# untitled.net
KiCad netlist of a schematic drawn in EAGLE
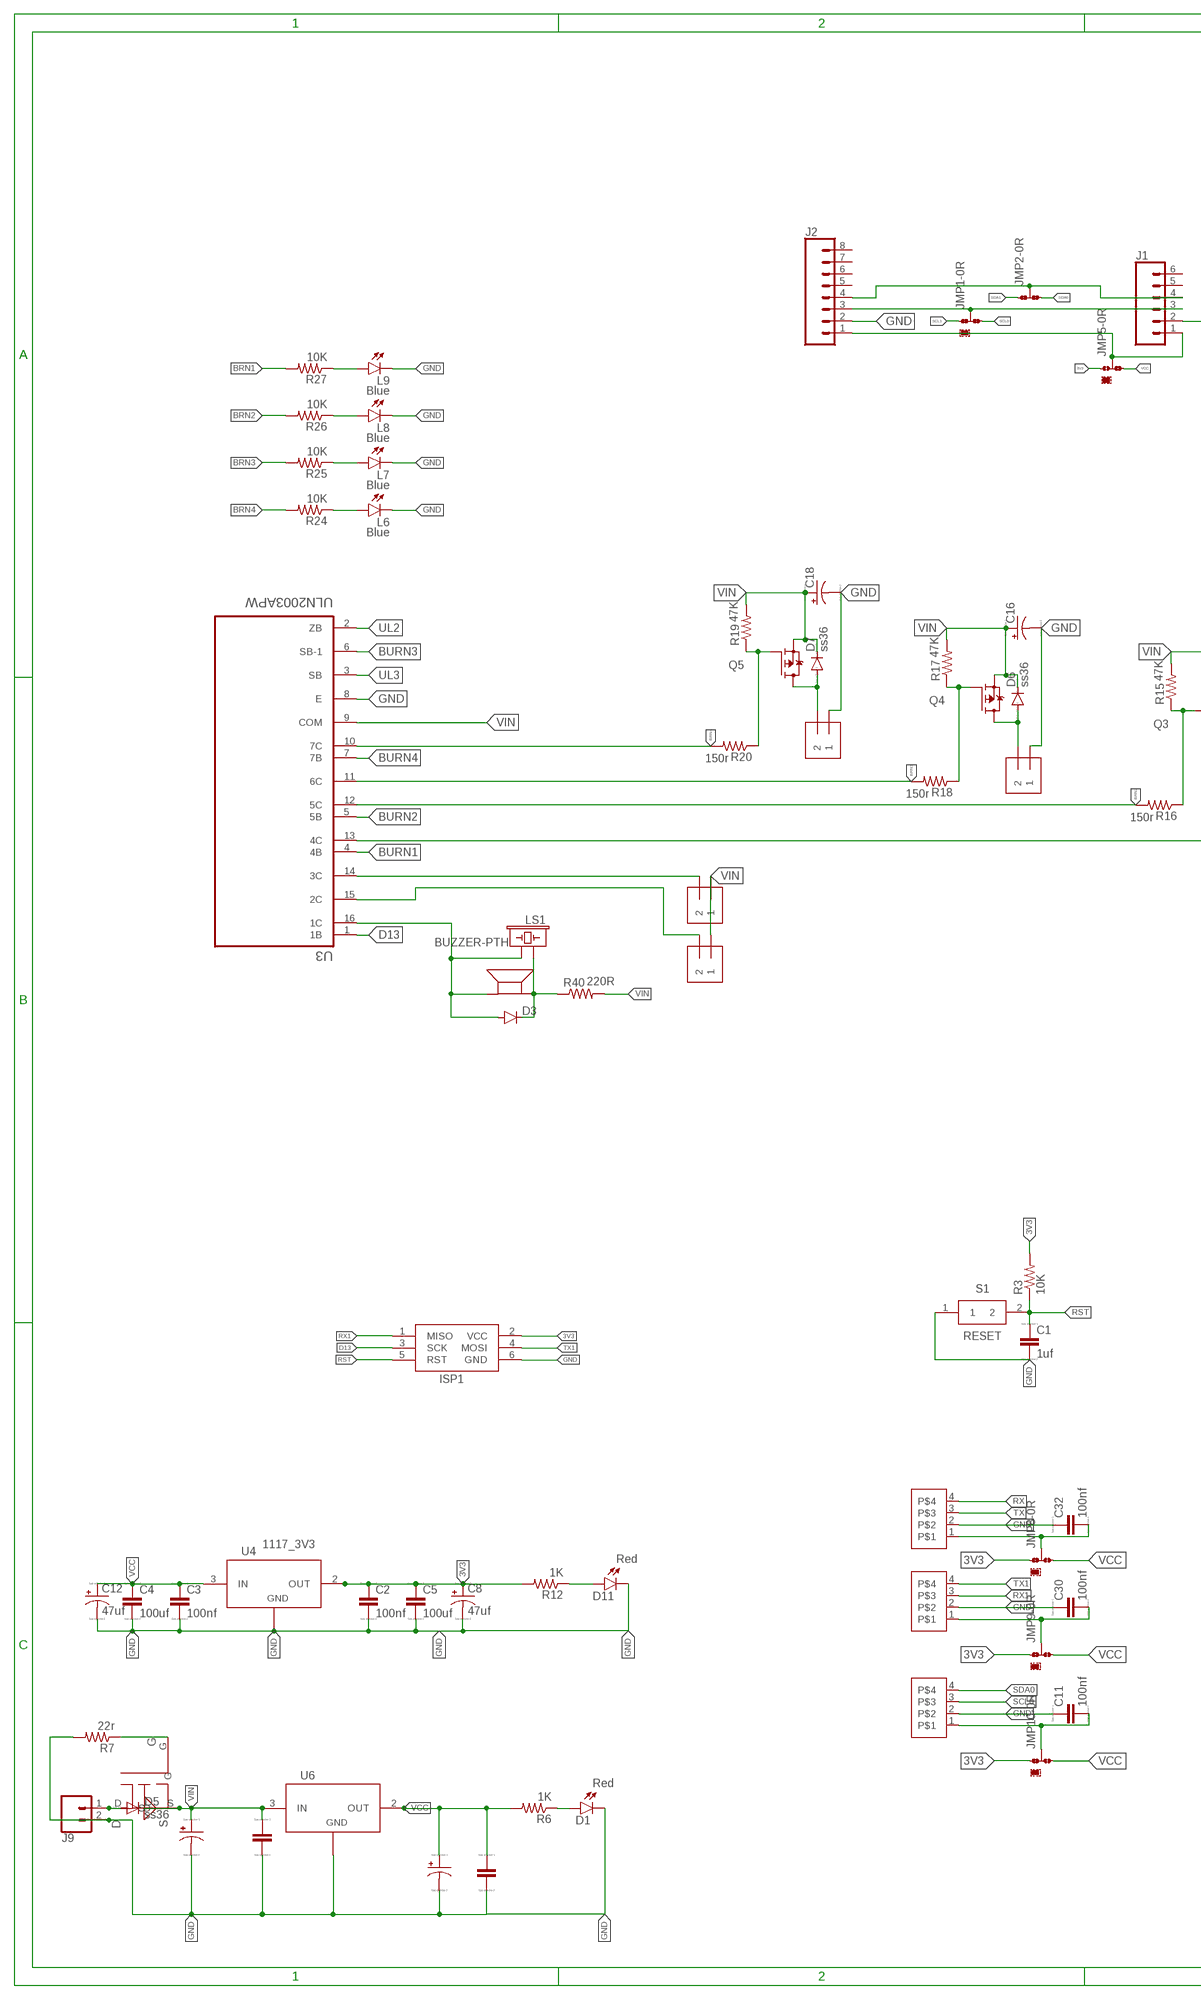
[diagram p0: schematic, sheet 1, part 1 of 2]
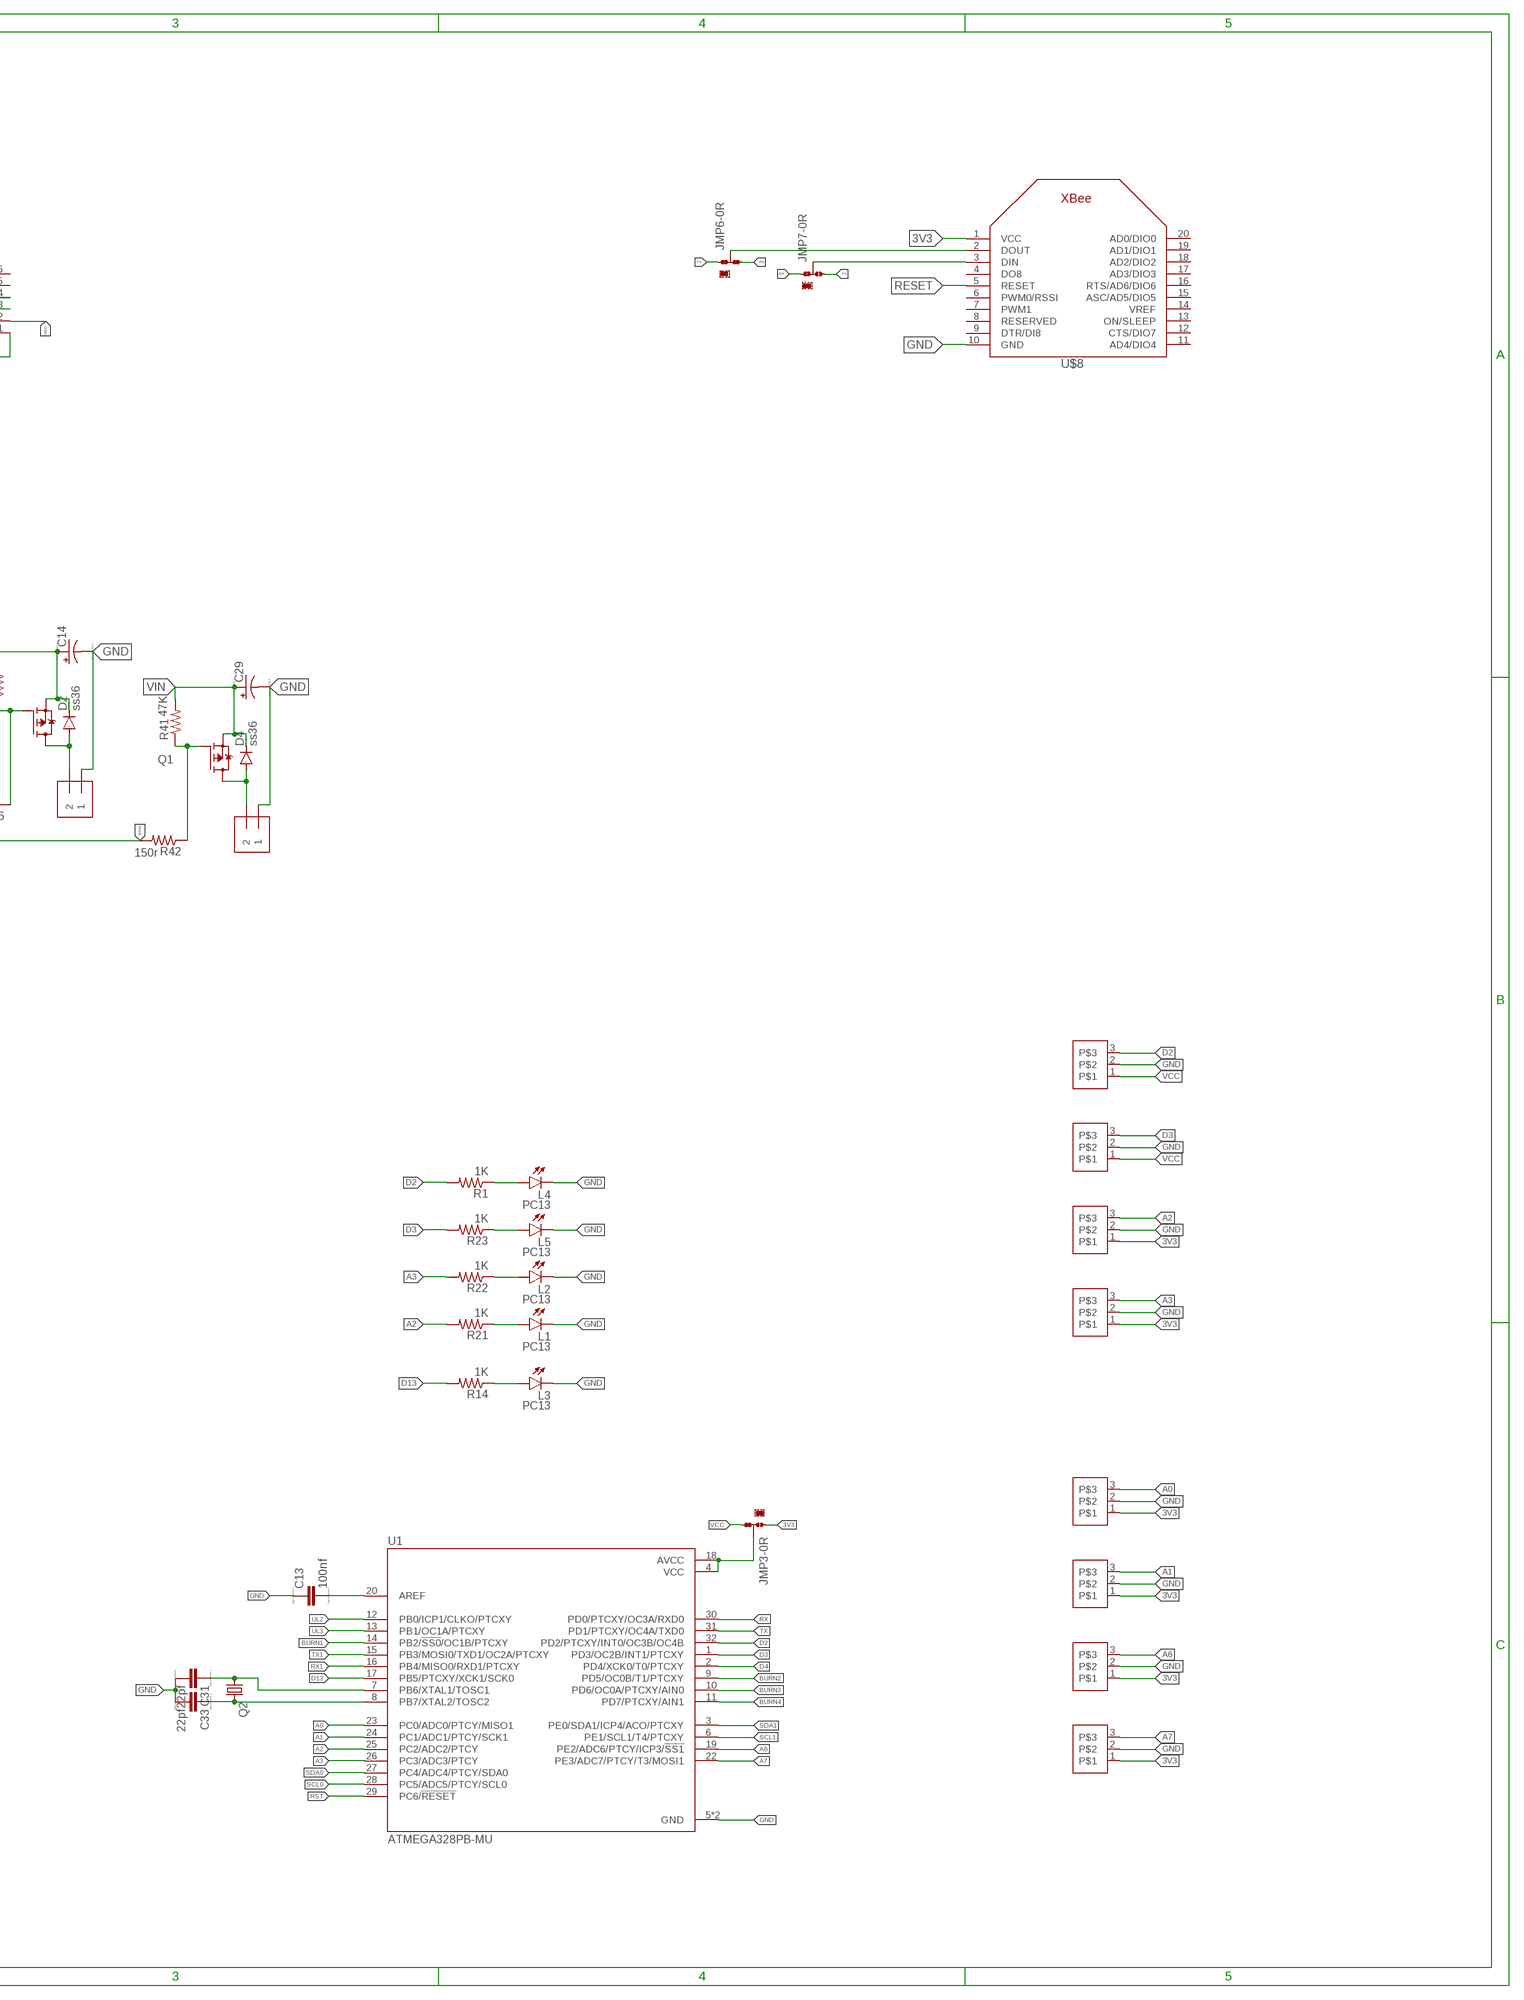
[diagram p1: schematic, sheet 1, part 2 of 2]

(export (version "E")
  (design (tool "Eeschema 10.0.6"))
  (components
    (comp (ref "C1")
      (value "1uf")
      (footprint "eagle-import:C0603")
      (libsource (lib "eagle-import") (part "CAPACITOR_CER4"))
    )
    (comp (ref "C2")
      (value "100nf")
      (footprint "eagle-import:C0603")
      (libsource (lib "eagle-import") (part "CAPACITOR_CER4"))
    )
    (comp (ref "C3")
      (value "100nf")
      (footprint "eagle-import:C0603")
      (libsource (lib "eagle-import") (part "CAPACITOR_CER4"))
    )
    (comp (ref "C4")
      (value "100uf")
      (footprint "eagle-import:C1210")
      (libsource (lib "eagle-import") (part "CAPACITOR_CER9"))
    )
    (comp (ref "C5")
      (value "100uf")
      (footprint "eagle-import:C1210")
      (libsource (lib "eagle-import") (part "CAPACITOR_CER9"))
    )
    (comp (ref "C6")
      (value "100nf")
      (footprint "eagle-import:C0603")
      (libsource (lib "eagle-import") (part "CAPACITOR_CER4"))
    )
    (comp (ref "C7")
      (value "100uf")
      (footprint "eagle-import:PANASONIC_D")
      (libsource (lib "eagle-import") (part "CAPACITOR_POLD"))
    )
    (comp (ref "C8")
      (value "47uf")
      (footprint "eagle-import:PANASONIC_C")
      (libsource (lib "eagle-import") (part "CAPACITOR_POLC"))
    )
    (comp (ref "C9")
      (value "100nf")
      (footprint "eagle-import:C0603")
      (libsource (lib "eagle-import") (part "CAPACITOR_CER4"))
    )
    (comp (ref "C10")
      (value "100uf")
      (footprint "eagle-import:PANASONIC_D")
      (libsource (lib "eagle-import") (part "CAPACITOR_POLD"))
    )
    (comp (ref "C11")
      (value "100nf")
      (footprint "eagle-import:C0603")
      (libsource (lib "eagle-import") (part "CAPACITOR_CER4"))
    )
    (comp (ref "C12")
      (value "47uf")
      (footprint "eagle-import:PANASONIC_C")
      (libsource (lib "eagle-import") (part "CAPACITOR_POLC"))
    )
    (comp (ref "C13")
      (value "100nf")
      (footprint "eagle-import:C0603")
      (libsource (lib "eagle-import") (part "CAPACITOR_CER4"))
    )
    (comp (ref "C14")
      (value "CAPACITOR_POLC")
      (footprint "eagle-import:PANASONIC_C")
      (libsource (lib "eagle-import") (part "CAPACITOR_POLC"))
    )
    (comp (ref "C16")
      (value "CAPACITOR_POLC")
      (footprint "eagle-import:PANASONIC_C")
      (libsource (lib "eagle-import") (part "CAPACITOR_POLC"))
    )
    (comp (ref "C18")
      (value "CAPACITOR_POLC")
      (footprint "eagle-import:PANASONIC_C")
      (libsource (lib "eagle-import") (part "CAPACITOR_POLC"))
    )
    (comp (ref "C29")
      (value "CAPACITOR_POLC")
      (footprint "eagle-import:PANASONIC_C")
      (libsource (lib "eagle-import") (part "CAPACITOR_POLC"))
    )
    (comp (ref "C30")
      (value "100nf")
      (footprint "eagle-import:C0603")
      (libsource (lib "eagle-import") (part "CAPACITOR_CER4"))
    )
    (comp (ref "C31")
      (value "22pf")
      (footprint "eagle-import:C0603")
      (libsource (lib "eagle-import") (part "CAPACITOR_CER4"))
    )
    (comp (ref "C32")
      (value "100nf")
      (footprint "eagle-import:C0603")
      (libsource (lib "eagle-import") (part "CAPACITOR_CER4"))
    )
    (comp (ref "C33")
      (value "22pf")
      (footprint "eagle-import:C0603")
      (libsource (lib "eagle-import") (part "CAPACITOR_CER4"))
    )
    (comp (ref "D1")
      (value "Red")
      (footprint "eagle-import:0603_LED_GREEN")
      (libsource (lib "eagle-import") (part "LED0603_R"))
    )
    (comp (ref "D2")
      (value "ss36")
      (footprint "eagle-import:DO-214AC")
      (libsource (lib "eagle-import") (part "DIODEAC2"))
    )
    (comp (ref "D3")
      (value "DIODESOD")
      (footprint "eagle-import:SOD-323")
      (libsource (lib "eagle-import") (part "DIODESOD"))
    )
    (comp (ref "D4")
      (value "ss36")
      (footprint "eagle-import:DO-214AC")
      (libsource (lib "eagle-import") (part "DIODEAC2"))
    )
    (comp (ref "D5")
      (value "ss36")
      (footprint "eagle-import:DO-214AC")
      (libsource (lib "eagle-import") (part "DIODEAC2"))
    )
    (comp (ref "D6")
      (value "ss36")
      (footprint "eagle-import:DO-214AC")
      (libsource (lib "eagle-import") (part "DIODEAC2"))
    )
    (comp (ref "D7")
      (value "ss36")
      (footprint "eagle-import:DO-214AC")
      (libsource (lib "eagle-import") (part "DIODEAC2"))
    )
    (comp (ref "D11")
      (value "Red")
      (footprint "eagle-import:0603_LED_GREEN")
      (libsource (lib "eagle-import") (part "LED0603_R"))
    )
    (comp (ref "ISP1")
      (value "AVRISP-6")
      (footprint "eagle-import:AVRISP")
      (libsource (lib "eagle-import") (part "AVRISP-6"))
    )
    (comp (ref "J1")
      (value "CONN_06NO_SILK_NO_POP")
      (footprint "eagle-import:1X06_NO_SILK")
      (libsource (lib "eagle-import") (part "CONN_06NO_SILK_NO_POP"))
    )
    (comp (ref "J2")
      (value "CONN_08NO_SILK_FEMALE_PTH")
      (footprint "eagle-import:1X08_NO_SILK")
      (libsource (lib "eagle-import") (part "CONN_08NO_SILK_FEMALE_PTH"))
    )
    (comp (ref "J9")
      (value "CONN_025MM")
      (footprint "eagle-import:SCREWTERMINAL-5MM-2")
      (libsource (lib "eagle-import") (part "CONN_025MM"))
    )
    (comp (ref "JMP1")
      (value "0R-JUMPA")
      (footprint "eagle-import:A0R-JMP")
      (libsource (lib "eagle-import") (part "0R-JUMPA"))
    )
    (comp (ref "JMP2")
      (value "0R-JUMPA")
      (footprint "eagle-import:A0R-JMP")
      (libsource (lib "eagle-import") (part "0R-JUMPA"))
    )
    (comp (ref "JMP3")
      (value "0R-JUMPA")
      (footprint "eagle-import:A0R-JMP")
      (libsource (lib "eagle-import") (part "0R-JUMPA"))
    )
    (comp (ref "JMP5")
      (value "0R-JUMPA")
      (footprint "eagle-import:A0R-JMP")
      (libsource (lib "eagle-import") (part "0R-JUMPA"))
    )
    (comp (ref "JMP6")
      (value "0R-JUMPA")
      (footprint "eagle-import:A0R-JMP")
      (libsource (lib "eagle-import") (part "0R-JUMPA"))
    )
    (comp (ref "JMP7")
      (value "0R-JUMPA")
      (footprint "eagle-import:A0R-JMP")
      (libsource (lib "eagle-import") (part "0R-JUMPA"))
    )
    (comp (ref "JMP8")
      (value "0R-JUMPA")
      (footprint "eagle-import:A0R-JMP")
      (libsource (lib "eagle-import") (part "0R-JUMPA"))
    )
    (comp (ref "JMP9")
      (value "0R-JUMPA")
      (footprint "eagle-import:A0R-JMP")
      (libsource (lib "eagle-import") (part "0R-JUMPA"))
    )
    (comp (ref "JMP10")
      (value "0R-JUMPA")
      (footprint "eagle-import:A0R-JMP")
      (libsource (lib "eagle-import") (part "0R-JUMPA"))
    )
    (comp (ref "L1")
      (value "PC13")
      (footprint "eagle-import:0603_LED_GREEN")
      (libsource (lib "eagle-import") (part "LED0603_R"))
    )
    (comp (ref "L2")
      (value "PC13")
      (footprint "eagle-import:0603_LED_GREEN")
      (libsource (lib "eagle-import") (part "LED0603_R"))
    )
    (comp (ref "L3")
      (value "PC13")
      (footprint "eagle-import:0603_LED_GREEN")
      (libsource (lib "eagle-import") (part "LED0603_R"))
    )
    (comp (ref "L4")
      (value "PC13")
      (footprint "eagle-import:0603_LED_GREEN")
      (libsource (lib "eagle-import") (part "LED0603_R"))
    )
    (comp (ref "L5")
      (value "PC13")
      (footprint "eagle-import:0603_LED_GREEN")
      (libsource (lib "eagle-import") (part "LED0603_R"))
    )
    (comp (ref "L6")
      (value "Blue")
      (footprint "eagle-import:0603_LED_GREEN")
      (libsource (lib "eagle-import") (part "LED0603_R"))
    )
    (comp (ref "L7")
      (value "Blue")
      (footprint "eagle-import:0603_LED_GREEN")
      (libsource (lib "eagle-import") (part "LED0603_R"))
    )
    (comp (ref "L8")
      (value "Blue")
      (footprint "eagle-import:0603_LED_GREEN")
      (libsource (lib "eagle-import") (part "LED0603_R"))
    )
    (comp (ref "L9")
      (value "Blue")
      (footprint "eagle-import:0603_LED_GREEN")
      (libsource (lib "eagle-import") (part "LED0603_R"))
    )
    (comp (ref "LS1")
      (value "BUZZER-PTH")
      (footprint "eagle-import:BUZZER-12MM")
      (libsource (lib "eagle-import") (part "BUZZER-PTH"))
    )
    (comp (ref "Q1")
      (value "FDD4141TO252")
      (footprint "eagle-import:TO252")
      (libsource (lib "eagle-import") (part "FDD4141TO252"))
    )
    (comp (ref "Q2")
      (value "CRYSTALHC49U-V")
      (footprint "eagle-import:HC49U-V")
      (libsource (lib "eagle-import") (part "CRYSTALHC49U-V"))
    )
    (comp (ref "Q3")
      (value "FDD4141TO252")
      (footprint "eagle-import:TO252")
      (libsource (lib "eagle-import") (part "FDD4141TO252"))
    )
    (comp (ref "Q4")
      (value "FDD4141TO252")
      (footprint "eagle-import:TO252")
      (libsource (lib "eagle-import") (part "FDD4141TO252"))
    )
    (comp (ref "Q5")
      (value "FDD4141TO252")
      (footprint "eagle-import:TO252")
      (libsource (lib "eagle-import") (part "FDD4141TO252"))
    )
    (comp (ref "Q6")
      (value "AON7401")
      (footprint "eagle-import:DFN-8_3X3")
      (libsource (lib "eagle-import") (part "AON7401"))
    )
    (comp (ref "R1")
      (value "1K")
      (footprint "eagle-import:R0603")
      (libsource (lib "eagle-import") (part "RESISTOR0603"))
    )
    (comp (ref "R3")
      (value "10K")
      (footprint "eagle-import:R0603")
      (libsource (lib "eagle-import") (part "RESISTOR0603"))
    )
    (comp (ref "R6")
      (value "1K")
      (footprint "eagle-import:R0603")
      (libsource (lib "eagle-import") (part "RESISTOR0603"))
    )
    (comp (ref "R7")
      (value "22r")
      (footprint "eagle-import:R0603")
      (libsource (lib "eagle-import") (part "RESISTOR0603"))
    )
    (comp (ref "R12")
      (value "1K")
      (footprint "eagle-import:R0603")
      (libsource (lib "eagle-import") (part "RESISTOR0603"))
    )
    (comp (ref "R14")
      (value "1K")
      (footprint "eagle-import:R0603")
      (libsource (lib "eagle-import") (part "RESISTOR0603"))
    )
    (comp (ref "R15")
      (value "47K")
      (footprint "eagle-import:R0603")
      (libsource (lib "eagle-import") (part "RESISTOR0603"))
    )
    (comp (ref "R16")
      (value "150r")
      (footprint "eagle-import:R0603")
      (libsource (lib "eagle-import") (part "RESISTOR0603"))
    )
    (comp (ref "R17")
      (value "47K")
      (footprint "eagle-import:R0603")
      (libsource (lib "eagle-import") (part "RESISTOR0603"))
    )
    (comp (ref "R18")
      (value "150r")
      (footprint "eagle-import:R0603")
      (libsource (lib "eagle-import") (part "RESISTOR0603"))
    )
    (comp (ref "R19")
      (value "47K")
      (footprint "eagle-import:R0603")
      (libsource (lib "eagle-import") (part "RESISTOR0603"))
    )
    (comp (ref "R20")
      (value "150r")
      (footprint "eagle-import:R0603")
      (libsource (lib "eagle-import") (part "RESISTOR0603"))
    )
    (comp (ref "R21")
      (value "1K")
      (footprint "eagle-import:R0603")
      (libsource (lib "eagle-import") (part "RESISTOR0603"))
    )
    (comp (ref "R22")
      (value "1K")
      (footprint "eagle-import:R0603")
      (libsource (lib "eagle-import") (part "RESISTOR0603"))
    )
    (comp (ref "R23")
      (value "1K")
      (footprint "eagle-import:R0603")
      (libsource (lib "eagle-import") (part "RESISTOR0603"))
    )
    (comp (ref "R24")
      (value "10K")
      (footprint "eagle-import:R0603")
      (libsource (lib "eagle-import") (part "RESISTOR0603"))
    )
    (comp (ref "R25")
      (value "10K")
      (footprint "eagle-import:R0603")
      (libsource (lib "eagle-import") (part "RESISTOR0603"))
    )
    (comp (ref "R26")
      (value "10K")
      (footprint "eagle-import:R0603")
      (libsource (lib "eagle-import") (part "RESISTOR0603"))
    )
    (comp (ref "R27")
      (value "10K")
      (footprint "eagle-import:R0603")
      (libsource (lib "eagle-import") (part "RESISTOR0603"))
    )
    (comp (ref "R40")
      (value "220R")
      (footprint "eagle-import:R0603")
      (libsource (lib "eagle-import") (part "RESISTOR0603"))
    )
    (comp (ref "R41")
      (value "47K")
      (footprint "eagle-import:R0603")
      (libsource (lib "eagle-import") (part "RESISTOR0603"))
    )
    (comp (ref "R42")
      (value "150r")
      (footprint "eagle-import:R0603")
      (libsource (lib "eagle-import") (part "RESISTOR0603"))
    )
    (comp (ref "S1")
      (value "RESET")
      (footprint "eagle-import:SKRK")
      (fields (field (name "MF") "ALPS") (field (name "MP") "SKRKAEE010"))
      (libsource (lib "eagle-import") (part "SKRKAEE010"))
    )
    (comp (ref "U$1")
      (value "Z_STOP")
      (footprint "eagle-import:HDRVR3W64P254_1X3_762X240X800B")
      (libsource (lib "eagle-import") (part "FML_1X3"))
    )
    (comp (ref "U$2")
      (value "Y_STOP")
      (footprint "eagle-import:HDRVR3W64P254_1X3_762X240X800B")
      (libsource (lib "eagle-import") (part "FML_1X3"))
    )
    (comp (ref "U$3")
      (value "X_STOP")
      (footprint "eagle-import:HDRVR3W64P254_1X3_762X240X800B")
      (libsource (lib "eagle-import") (part "FML_1X3"))
    )
    (comp (ref "U$4")
      (value "1X2")
      (footprint "eagle-import:1X2")
      (libsource (lib "eagle-import") (part "1X2"))
    )
    (comp (ref "U$5")
      (value "1X2")
      (footprint "eagle-import:1X2")
      (libsource (lib "eagle-import") (part "1X2"))
    )
    (comp (ref "U$6")
      (value "1X2")
      (footprint "eagle-import:1X2")
      (libsource (lib "eagle-import") (part "1X2"))
    )
    (comp (ref "U$7")
      (value "FML_1X4")
      (footprint "eagle-import:HDRVR4W64P254_1X4_1016X240X800B")
      (libsource (lib "eagle-import") (part "FML_1X4"))
    )
    (comp (ref "U$8")
      (value "XBEE")
      (footprint "eagle-import:XBEE")
      (libsource (lib "eagle-import") (part "XBEE"))
    )
    (comp (ref "U$9")
      (value "Z_STOP")
      (footprint "eagle-import:HDRVR3W64P254_1X3_762X240X800B")
      (libsource (lib "eagle-import") (part "FML_1X3"))
    )
    (comp (ref "U$10")
      (value "Z_STOP")
      (footprint "eagle-import:HDRVR3W64P254_1X3_762X240X800B")
      (libsource (lib "eagle-import") (part "FML_1X3"))
    )
    (comp (ref "U$11")
      (value "FML_1X4")
      (footprint "eagle-import:HDRVR4W64P254_1X4_1016X240X800B")
      (libsource (lib "eagle-import") (part "FML_1X4"))
    )
    (comp (ref "U$12")
      (value "FML_1X4")
      (footprint "eagle-import:HDRVR4W64P254_1X4_1016X240X800B")
      (libsource (lib "eagle-import") (part "FML_1X4"))
    )
    (comp (ref "U$13")
      (value "Z_STOP")
      (footprint "eagle-import:HDRVR3W64P254_1X3_762X240X800B")
      (libsource (lib "eagle-import") (part "FML_1X3"))
    )
    (comp (ref "U$14")
      (value "Y_STOP")
      (footprint "eagle-import:HDRVR3W64P254_1X3_762X240X800B")
      (libsource (lib "eagle-import") (part "FML_1X3"))
    )
    (comp (ref "U$15")
      (value "X_STOP")
      (footprint "eagle-import:HDRVR3W64P254_1X3_762X240X800B")
      (libsource (lib "eagle-import") (part "FML_1X3"))
    )
    (comp (ref "U$19")
      (value "7.5X7.5_BUZZER")
      (footprint "eagle-import:SMD_7.5_BUZZER")
      (libsource (lib "eagle-import") (part "7.5X7.5_BUZZER"))
    )
    (comp (ref "U$20")
      (value "1X2")
      (footprint "eagle-import:1X2")
      (libsource (lib "eagle-import") (part "1X2"))
    )
    (comp (ref "U$21")
      (value "1X2")
      (footprint "eagle-import:1X2")
      (libsource (lib "eagle-import") (part "1X2"))
    )
    (comp (ref "U$22")
      (value "1X2")
      (footprint "eagle-import:1X2")
      (libsource (lib "eagle-import") (part "1X2"))
    )
    (comp (ref "U1")
      (value "ATMEGA328PB-MU")
      (footprint "eagle-import:QFN50P500X500X90-33N")
      (fields (field (name "MF") "Microchip"))
      (libsource (lib "eagle-import") (part "ATMEGA328PB-MU"))
    )
    (comp (ref "U3")
      (value "ULN2003APW")
      (footprint "eagle-import:SOP65P640X120-16N")
      (fields (field (name "MF") "Texas Instruments"))
      (libsource (lib "eagle-import") (part "ULN2003APW"))
    )
    (comp (ref "U4")
      (value "1117_3V3")
      (footprint "eagle-import:SOT-223")
      (fields
        (field (name "DIGIKEY_PART_NUMBER") "NCP1117ST33T3GOSTR-ND")
        (field (name "MANUFACTURER") "ON Semiconductor")
        (field (name "MPN") "NCP1117ST33T3G")
        (field (name "CREATED_BY") "PCBLayout.com")
      )
      (libsource (lib "eagle-import") (part "NCP1117ST33T3G"))
    )
    (comp (ref "U6")
      (value "1117_3V3")
      (footprint "eagle-import:SOT-223")
      (fields
        (field (name "DIGIKEY_PART_NUMBER") "NCP1117ST33T3GOSTR-ND")
        (field (name "MANUFACTURER") "ON Semiconductor")
        (field (name "MPN") "NCP1117ST33T3G")
        (field (name "CREATED_BY") "PCBLayout.com")
      )
      (libsource (lib "eagle-import") (part "NCP1117ST33T3G"))
    )
  )
  (nets
    (net (code "1") (name "3V3") (class "Default")
      (node (ref "C2") (pin "1") (pinfunction "1_1") (pintype "passive"))
      (node (ref "C5") (pin "1") (pinfunction "1_1") (pintype "passive"))
      (node (ref "C8") (pin "+") (pinfunction "+_+") (pintype "passive"))
      (node (ref "ISP1") (pin "2") (pinfunction "VCC_2") (pintype "power_in"))
      (node (ref "JMP10") (pin "1") (pinfunction "1_1") (pintype "passive"))
      (node (ref "JMP3") (pin "1") (pinfunction "1_1") (pintype "passive"))
      (node (ref "JMP5") (pin "1") (pinfunction "1_1") (pintype "passive"))
      (node (ref "JMP8") (pin "1") (pinfunction "1_1") (pintype "passive"))
      (node (ref "JMP9") (pin "1") (pinfunction "1_1") (pintype "passive"))
      (node (ref "R12") (pin "2") (pinfunction "2_2") (pintype "passive"))
      (node (ref "R3") (pin "2") (pinfunction "2_2") (pintype "passive"))
      (node (ref "U$13") (pin "1") (pinfunction "P$1_1") (pintype "bidirectional"))
      (node (ref "U$14") (pin "1") (pinfunction "P$1_1") (pintype "bidirectional"))
      (node (ref "U$15") (pin "1") (pinfunction "P$1_1") (pintype "bidirectional"))
      (node (ref "U$2") (pin "1") (pinfunction "P$1_1") (pintype "bidirectional"))
      (node (ref "U$3") (pin "1") (pinfunction "P$1_1") (pintype "bidirectional"))
      (node (ref "U$8") (pin "1") (pinfunction "VCC_1") (pintype "power_in"))
      (node (ref "U$9") (pin "1") (pinfunction "P$1_1") (pintype "bidirectional"))
      (node (ref "U4") (pin "2") (pinfunction "OUT_2") (pintype "output"))
      (node (ref "U4") (pin "4") (pinfunction "4_4") (pintype "passive"))
    )
    (net (code "2") (name "A0") (class "Default")
      (node (ref "U$9") (pin "3") (pinfunction "P$3_3") (pintype "bidirectional"))
      (node (ref "U1") (pin "23") (pinfunction "PC0/ADC0/PTCY/MISO1_23") (pintype "bidirectional"))
    )
    (net (code "3") (name "A1") (class "Default")
      (node (ref "U$13") (pin "3") (pinfunction "P$3_3") (pintype "bidirectional"))
      (node (ref "U1") (pin "24") (pinfunction "PC1/ADC1/PTCY/SCK1_24") (pintype "bidirectional"))
    )
    (net (code "4") (name "A2") (class "Default")
      (node (ref "R21") (pin "2") (pinfunction "2_2") (pintype "passive"))
      (node (ref "U$2") (pin "3") (pinfunction "P$3_3") (pintype "bidirectional"))
      (node (ref "U1") (pin "25") (pinfunction "PC2/ADC2/PTCY_25") (pintype "bidirectional"))
    )
    (net (code "5") (name "A3") (class "Default")
      (node (ref "R22") (pin "2") (pinfunction "2_2") (pintype "passive"))
      (node (ref "U$3") (pin "3") (pinfunction "P$3_3") (pintype "bidirectional"))
      (node (ref "U1") (pin "26") (pinfunction "PC3/ADC3/PTCY_26") (pintype "bidirectional"))
    )
    (net (code "6") (name "A6") (class "Default")
      (node (ref "U$14") (pin "3") (pinfunction "P$3_3") (pintype "bidirectional"))
      (node (ref "U1") (pin "19") (pinfunction "PE2/ADC6/PTCY/ICP3/~{SS1}_19") (pintype "bidirectional"))
    )
    (net (code "7") (name "A7") (class "Default")
      (node (ref "U$15") (pin "3") (pinfunction "P$3_3") (pintype "bidirectional"))
      (node (ref "U1") (pin "22") (pinfunction "PE3/ADC7/PTCY/T3/MOSI1_22") (pintype "bidirectional"))
    )
    (net (code "8") (name "BRN1") (class "Default")
      (node (ref "R27") (pin "2") (pinfunction "2_2") (pintype "passive"))
      (node (ref "R42") (pin "2") (pinfunction "2_2") (pintype "passive"))
      (node (ref "U3") (pin "13") (pinfunction "4C_13") (pintype "bidirectional"))
    )
    (net (code "9") (name "BRN2") (class "Default")
      (node (ref "R16") (pin "2") (pinfunction "2_2") (pintype "passive"))
      (node (ref "R26") (pin "2") (pinfunction "2_2") (pintype "passive"))
      (node (ref "U3") (pin "12") (pinfunction "5C_12") (pintype "bidirectional"))
    )
    (net (code "10") (name "BRN3") (class "Default")
      (node (ref "R18") (pin "2") (pinfunction "2_2") (pintype "passive"))
      (node (ref "R25") (pin "2") (pinfunction "2_2") (pintype "passive"))
      (node (ref "U3") (pin "11") (pinfunction "6C_11") (pintype "bidirectional"))
    )
    (net (code "11") (name "BRN4") (class "Default")
      (node (ref "R20") (pin "2") (pinfunction "2_2") (pintype "passive"))
      (node (ref "R24") (pin "2") (pinfunction "2_2") (pintype "passive"))
      (node (ref "U3") (pin "10") (pinfunction "7C_10") (pintype "bidirectional"))
    )
    (net (code "12") (name "BURN1") (class "Default")
      (node (ref "U1") (pin "14") (pinfunction "PB2/~{SS0}/OC1B/PTCXY_14") (pintype "bidirectional"))
      (node (ref "U3") (pin "4") (pinfunction "4B_4") (pintype "bidirectional"))
    )
    (net (code "13") (name "BURN2") (class "Default")
      (node (ref "U1") (pin "9") (pinfunction "PD5/OC0B/T1/PTCXY_9") (pintype "bidirectional"))
      (node (ref "U3") (pin "5") (pinfunction "5B_5") (pintype "bidirectional"))
    )
    (net (code "14") (name "BURN3") (class "Default")
      (node (ref "U1") (pin "10") (pinfunction "PD6/OC0A/PTCXY/AIN0_10") (pintype "bidirectional"))
      (node (ref "U3") (pin "6") (pinfunction "SB-1_6") (pintype "bidirectional"))
    )
    (net (code "15") (name "BURN4") (class "Default")
      (node (ref "U1") (pin "11") (pinfunction "PD7/PTCXY/AIN1_11") (pintype "bidirectional"))
      (node (ref "U3") (pin "7") (pinfunction "7B_7") (pintype "bidirectional"))
    )
    (net (code "16") (name "D2") (class "Default")
      (node (ref "R1") (pin "2") (pinfunction "2_2") (pintype "passive"))
      (node (ref "U$10") (pin "3") (pinfunction "P$3_3") (pintype "bidirectional"))
      (node (ref "U1") (pin "32") (pinfunction "PD2/PTCXY/INT0/OC3B/OC4B_32") (pintype "bidirectional"))
    )
    (net (code "17") (name "D3") (class "Default")
      (node (ref "R23") (pin "2") (pinfunction "2_2") (pintype "passive"))
      (node (ref "U$1") (pin "3") (pinfunction "P$3_3") (pintype "bidirectional"))
      (node (ref "U1") (pin "1") (pinfunction "PD3/OC2B/INT1/PTCXY_1") (pintype "bidirectional"))
    )
    (net (code "18") (name "D4") (class "Default")
      (node (ref "U1") (pin "2") (pinfunction "PD4/XCK0/T0/PTCXY_2") (pintype "bidirectional"))
    )
    (net (code "19") (name "D13") (class "Default")
      (node (ref "ISP1") (pin "3") (pinfunction "SCK_3") (pintype "output"))
      (node (ref "R14") (pin "2") (pinfunction "2_2") (pintype "passive"))
      (node (ref "U1") (pin "17") (pinfunction "PB5/PTCXY/XCK1/SCK0_17") (pintype "bidirectional"))
      (node (ref "U3") (pin "1") (pinfunction "1B_1") (pintype "bidirectional"))
    )
    (net (code "20") (name "GND") (class "Default")
      (node (ref "C1") (pin "2") (pinfunction "2_2") (pintype "passive"))
      (node (ref "C10") (pin "-") (pinfunction "-_-") (pintype "passive"))
      (node (ref "C11") (pin "1") (pinfunction "1_1") (pintype "passive"))
      (node (ref "C12") (pin "-") (pinfunction "-_-") (pintype "passive"))
      (node (ref "C13") (pin "1") (pinfunction "1_1") (pintype "passive"))
      (node (ref "C14") (pin "-") (pinfunction "-_-") (pintype "passive"))
      (node (ref "C16") (pin "-") (pinfunction "-_-") (pintype "passive"))
      (node (ref "C18") (pin "-") (pinfunction "-_-") (pintype "passive"))
      (node (ref "C2") (pin "2") (pinfunction "2_2") (pintype "passive"))
      (node (ref "C29") (pin "-") (pinfunction "-_-") (pintype "passive"))
      (node (ref "C3") (pin "2") (pinfunction "2_2") (pintype "passive"))
      (node (ref "C30") (pin "1") (pinfunction "1_1") (pintype "passive"))
      (node (ref "C31") (pin "2") (pinfunction "2_2") (pintype "passive"))
      (node (ref "C32") (pin "1") (pinfunction "1_1") (pintype "passive"))
      (node (ref "C33") (pin "2") (pinfunction "2_2") (pintype "passive"))
      (node (ref "C4") (pin "2") (pinfunction "2_2") (pintype "passive"))
      (node (ref "C5") (pin "2") (pinfunction "2_2") (pintype "passive"))
      (node (ref "C6") (pin "2") (pinfunction "2_2") (pintype "passive"))
      (node (ref "C7") (pin "-") (pinfunction "-_-") (pintype "passive"))
      (node (ref "C8") (pin "-") (pinfunction "-_-") (pintype "passive"))
      (node (ref "C9") (pin "2") (pinfunction "2_2") (pintype "passive"))
      (node (ref "D1") (pin "C") (pinfunction "C_C") (pintype "passive"))
      (node (ref "D11") (pin "C") (pinfunction "C_C") (pintype "passive"))
      (node (ref "ISP1") (pin "6") (pinfunction "GND_6") (pintype "power_in"))
      (node (ref "J1") (pin "2") (pinfunction "2_2") (pintype "passive"))
      (node (ref "J2") (pin "2") (pinfunction "2_2") (pintype "passive"))
      (node (ref "J9") (pin "2") (pinfunction "2_2") (pintype "passive"))
      (node (ref "L1") (pin "C") (pinfunction "C_C") (pintype "passive"))
      (node (ref "L2") (pin "C") (pinfunction "C_C") (pintype "passive"))
      (node (ref "L3") (pin "C") (pinfunction "C_C") (pintype "passive"))
      (node (ref "L4") (pin "C") (pinfunction "C_C") (pintype "passive"))
      (node (ref "L5") (pin "C") (pinfunction "C_C") (pintype "passive"))
      (node (ref "L6") (pin "C") (pinfunction "C_C") (pintype "passive"))
      (node (ref "L7") (pin "C") (pinfunction "C_C") (pintype "passive"))
      (node (ref "L8") (pin "C") (pinfunction "C_C") (pintype "passive"))
      (node (ref "L9") (pin "C") (pinfunction "C_C") (pintype "passive"))
      (node (ref "R7") (pin "2") (pinfunction "2_2") (pintype "passive"))
      (node (ref "S1") (pin "1") (pinfunction "1_1") (pintype "passive"))
      (node (ref "U$1") (pin "2") (pinfunction "P$2_2") (pintype "bidirectional"))
      (node (ref "U$10") (pin "2") (pinfunction "P$2_2") (pintype "bidirectional"))
      (node (ref "U$11") (pin "2") (pinfunction "P$2_2") (pintype "bidirectional"))
      (node (ref "U$12") (pin "2") (pinfunction "P$2_2") (pintype "bidirectional"))
      (node (ref "U$13") (pin "2") (pinfunction "P$2_2") (pintype "bidirectional"))
      (node (ref "U$14") (pin "2") (pinfunction "P$2_2") (pintype "bidirectional"))
      (node (ref "U$15") (pin "2") (pinfunction "P$2_2") (pintype "bidirectional"))
      (node (ref "U$2") (pin "2") (pinfunction "P$2_2") (pintype "bidirectional"))
      (node (ref "U$21") (pin "P$1") (pinfunction "1_P$1") (pintype "passive"))
      (node (ref "U$3") (pin "2") (pinfunction "P$2_2") (pintype "bidirectional"))
      (node (ref "U$4") (pin "P$1") (pinfunction "1_P$1") (pintype "passive"))
      (node (ref "U$5") (pin "P$1") (pinfunction "1_P$1") (pintype "passive"))
      (node (ref "U$6") (pin "P$1") (pinfunction "1_P$1") (pintype "passive"))
      (node (ref "U$7") (pin "2") (pinfunction "P$2_2") (pintype "bidirectional"))
      (node (ref "U$8") (pin "10") (pinfunction "GND_10") (pintype "power_in"))
      (node (ref "U$9") (pin "2") (pinfunction "P$2_2") (pintype "bidirectional"))
      (node (ref "U1") (pin "21") (pinfunction "GND_21") (pintype "power_in"))
      (node (ref "U1") (pin "5") (pinfunction "GND_5") (pintype "power_in"))
      (node (ref "U3") (pin "8") (pinfunction "E_8") (pintype "bidirectional"))
      (node (ref "U4") (pin "1") (pinfunction "ADJ/GND_1") (pintype "power_in"))
      (node (ref "U6") (pin "1") (pinfunction "ADJ/GND_1") (pintype "power_in"))
    )
    (net (code "21") (name "Net-(D1-PadA)") (class "Default")
      (node (ref "D1") (pin "A") (pinfunction "A_A") (pintype "passive"))
      (node (ref "R6") (pin "1") (pinfunction "1_1") (pintype "passive"))
    )
    (net (code "22") (name "Net-(D5-PadA)") (class "Default")
      (node (ref "D5") (pin "A") (pinfunction "A_A") (pintype "passive"))
      (node (ref "J9") (pin "1") (pinfunction "1_1") (pintype "passive"))
      (node (ref "Q6") (pin "D") (pinfunction "D_D") (pintype "bidirectional"))
    )
    (net (code "23") (name "Net-(D11-PadA)") (class "Default")
      (node (ref "D11") (pin "A") (pinfunction "A_A") (pintype "passive"))
      (node (ref "R12") (pin "1") (pinfunction "1_1") (pintype "passive"))
    )
    (net (code "24") (name "Net-(J1-Pad1)") (class "Default")
      (node (ref "J1") (pin "1") (pinfunction "1_1") (pintype "passive"))
      (node (ref "J2") (pin "1") (pinfunction "1_1") (pintype "passive"))
      (node (ref "JMP5") (pin "2") (pinfunction "2_2") (pintype "passive"))
    )
    (net (code "25") (name "Net-(J1-Pad3)") (class "Default")
      (node (ref "J1") (pin "3") (pinfunction "3_3") (pintype "passive"))
      (node (ref "J2") (pin "3") (pinfunction "3_3") (pintype "passive"))
      (node (ref "JMP1") (pin "2") (pinfunction "2_2") (pintype "passive"))
    )
    (net (code "26") (name "Net-(J1-Pad4)") (class "Default")
      (node (ref "J1") (pin "4") (pinfunction "4_4") (pintype "passive"))
      (node (ref "J2") (pin "4") (pinfunction "4_4") (pintype "passive"))
      (node (ref "JMP2") (pin "2") (pinfunction "2_2") (pintype "passive"))
    )
    (net (code "27") (name "Net-(L1-PadA)") (class "Default")
      (node (ref "L1") (pin "A") (pinfunction "A_A") (pintype "passive"))
      (node (ref "R21") (pin "1") (pinfunction "1_1") (pintype "passive"))
    )
    (net (code "28") (name "Net-(L2-PadA)") (class "Default")
      (node (ref "L2") (pin "A") (pinfunction "A_A") (pintype "passive"))
      (node (ref "R22") (pin "1") (pinfunction "1_1") (pintype "passive"))
    )
    (net (code "29") (name "Net-(L3-PadA)") (class "Default")
      (node (ref "L3") (pin "A") (pinfunction "A_A") (pintype "passive"))
      (node (ref "R14") (pin "1") (pinfunction "1_1") (pintype "passive"))
    )
    (net (code "30") (name "Net-(L4-PadA)") (class "Default")
      (node (ref "L4") (pin "A") (pinfunction "A_A") (pintype "passive"))
      (node (ref "R1") (pin "1") (pinfunction "1_1") (pintype "passive"))
    )
    (net (code "31") (name "Net-(L5-PadA)") (class "Default")
      (node (ref "L5") (pin "A") (pinfunction "A_A") (pintype "passive"))
      (node (ref "R23") (pin "1") (pinfunction "1_1") (pintype "passive"))
    )
    (net (code "32") (name "Net-(L6-PadA)") (class "Default")
      (node (ref "L6") (pin "A") (pinfunction "A_A") (pintype "passive"))
      (node (ref "R24") (pin "1") (pinfunction "1_1") (pintype "passive"))
    )
    (net (code "33") (name "Net-(L7-PadA)") (class "Default")
      (node (ref "L7") (pin "A") (pinfunction "A_A") (pintype "passive"))
      (node (ref "R25") (pin "1") (pinfunction "1_1") (pintype "passive"))
    )
    (net (code "34") (name "Net-(L8-PadA)") (class "Default")
      (node (ref "L8") (pin "A") (pinfunction "A_A") (pintype "passive"))
      (node (ref "R26") (pin "1") (pinfunction "1_1") (pintype "passive"))
    )
    (net (code "35") (name "Net-(L9-PadA)") (class "Default")
      (node (ref "L9") (pin "A") (pinfunction "A_A") (pintype "passive"))
      (node (ref "R27") (pin "1") (pinfunction "1_1") (pintype "passive"))
    )
    (net (code "36") (name "Net-(LS1-1)") (class "Default")
      (node (ref "D3") (pin "C") (pinfunction "C_C") (pintype "passive"))
      (node (ref "LS1") (pin "+") (pinfunction "1_+") (pintype "passive"))
      (node (ref "R40") (pin "1") (pinfunction "1_1") (pintype "passive"))
      (node (ref "U$19") (pin "+") (pinfunction "+_+") (pintype "bidirectional"))
    )
    (net (code "37") (name "Net-(LS1-2)") (class "Default")
      (node (ref "D3") (pin "A") (pinfunction "A_A") (pintype "passive"))
      (node (ref "LS1") (pin "-") (pinfunction "2_-") (pintype "passive"))
      (node (ref "U$19") (pin "-") (pinfunction "-_-") (pintype "bidirectional"))
      (node (ref "U3") (pin "16") (pinfunction "1C_16") (pintype "bidirectional"))
    )
    (net (code "38") (name "Net-(Q1-D)") (class "Default")
      (node (ref "D4") (pin "A") (pinfunction "A_A") (pintype "passive"))
      (node (ref "Q1") (pin "3") (pinfunction "D_3") (pintype "passive"))
      (node (ref "U$21") (pin "P$2") (pinfunction "2_P$2") (pintype "passive"))
    )
    (net (code "39") (name "Net-(Q1-G)") (class "Default")
      (node (ref "Q1") (pin "1") (pinfunction "G_1") (pintype "passive"))
      (node (ref "R41") (pin "1") (pinfunction "1_1") (pintype "passive"))
      (node (ref "R42") (pin "1") (pinfunction "1_1") (pintype "passive"))
    )
    (net (code "40") (name "Net-(Q3-D)") (class "Default")
      (node (ref "D2") (pin "A") (pinfunction "A_A") (pintype "passive"))
      (node (ref "Q3") (pin "3") (pinfunction "D_3") (pintype "passive"))
      (node (ref "U$4") (pin "P$2") (pinfunction "2_P$2") (pintype "passive"))
    )
    (net (code "41") (name "Net-(Q3-G)") (class "Default")
      (node (ref "Q3") (pin "1") (pinfunction "G_1") (pintype "passive"))
      (node (ref "R15") (pin "1") (pinfunction "1_1") (pintype "passive"))
      (node (ref "R16") (pin "1") (pinfunction "1_1") (pintype "passive"))
    )
    (net (code "42") (name "Net-(Q4-D)") (class "Default")
      (node (ref "D6") (pin "A") (pinfunction "A_A") (pintype "passive"))
      (node (ref "Q4") (pin "3") (pinfunction "D_3") (pintype "passive"))
      (node (ref "U$5") (pin "P$2") (pinfunction "2_P$2") (pintype "passive"))
    )
    (net (code "43") (name "Net-(Q4-G)") (class "Default")
      (node (ref "Q4") (pin "1") (pinfunction "G_1") (pintype "passive"))
      (node (ref "R17") (pin "1") (pinfunction "1_1") (pintype "passive"))
      (node (ref "R18") (pin "1") (pinfunction "1_1") (pintype "passive"))
    )
    (net (code "44") (name "Net-(Q5-D)") (class "Default")
      (node (ref "D7") (pin "A") (pinfunction "A_A") (pintype "passive"))
      (node (ref "Q5") (pin "3") (pinfunction "D_3") (pintype "passive"))
      (node (ref "U$6") (pin "P$2") (pinfunction "2_P$2") (pintype "passive"))
    )
    (net (code "45") (name "Net-(Q5-G)") (class "Default")
      (node (ref "Q5") (pin "1") (pinfunction "G_1") (pintype "passive"))
      (node (ref "R19") (pin "1") (pinfunction "1_1") (pintype "passive"))
      (node (ref "R20") (pin "1") (pinfunction "1_1") (pintype "passive"))
    )
    (net (code "46") (name "Net-(Q6-PadG)") (class "Default")
      (node (ref "Q6") (pin "G") (pinfunction "G_G") (pintype "bidirectional"))
      (node (ref "R7") (pin "1") (pinfunction "1_1") (pintype "passive"))
    )
    (net (code "47") (name "Net-(U$7-P$1)") (class "Default")
      (node (ref "C11") (pin "2") (pinfunction "2_2") (pintype "passive"))
      (node (ref "JMP10") (pin "2") (pinfunction "2_2") (pintype "passive"))
      (node (ref "U$7") (pin "1") (pinfunction "P$1_1") (pintype "bidirectional"))
    )
    (net (code "48") (name "Net-(U$8-DIN)") (class "Default")
      (node (ref "JMP7") (pin "2") (pinfunction "2_2") (pintype "passive"))
      (node (ref "U$8") (pin "3") (pinfunction "DIN_3") (pintype "input"))
    )
    (net (code "49") (name "Net-(U$8-DOUT)") (class "Default")
      (node (ref "JMP6") (pin "2") (pinfunction "2_2") (pintype "passive"))
      (node (ref "U$8") (pin "2") (pinfunction "DOUT_2") (pintype "output"))
    )
    (net (code "50") (name "Net-(U$11-P$1)") (class "Default")
      (node (ref "C32") (pin "2") (pinfunction "2_2") (pintype "passive"))
      (node (ref "JMP8") (pin "2") (pinfunction "2_2") (pintype "passive"))
      (node (ref "U$11") (pin "1") (pinfunction "P$1_1") (pintype "bidirectional"))
    )
    (net (code "51") (name "Net-(U$12-P$1)") (class "Default")
      (node (ref "C30") (pin "2") (pinfunction "2_2") (pintype "passive"))
      (node (ref "JMP9") (pin "2") (pinfunction "2_2") (pintype "passive"))
      (node (ref "U$12") (pin "1") (pinfunction "P$1_1") (pintype "bidirectional"))
    )
    (net (code "52") (name "Net-(U$20-2)") (class "Default")
      (node (ref "U$20") (pin "P$2") (pinfunction "2_P$2") (pintype "passive"))
      (node (ref "U3") (pin "15") (pinfunction "2C_15") (pintype "bidirectional"))
    )
    (net (code "53") (name "Net-(U$22-2)") (class "Default")
      (node (ref "U$22") (pin "P$2") (pinfunction "2_P$2") (pintype "passive"))
      (node (ref "U3") (pin "14") (pinfunction "3C_14") (pintype "bidirectional"))
    )
    (net (code "54") (name "Net-(U1-AREF)") (class "Default")
      (node (ref "C13") (pin "2") (pinfunction "2_2") (pintype "passive"))
      (node (ref "U1") (pin "20") (pinfunction "AREF_20") (pintype "input"))
    )
    (net (code "55") (name "Net-(U1-AVCC)") (class "Default")
      (node (ref "JMP3") (pin "2") (pinfunction "2_2") (pintype "passive"))
      (node (ref "U1") (pin "18") (pinfunction "AVCC_18") (pintype "power_in"))
      (node (ref "U1") (pin "4") (pinfunction "VCC_4") (pintype "power_in"))
    )
    (net (code "56") (name "Net-(U1-PB6{slash}XTAL1{slash}TOSC1)") (class "Default")
      (node (ref "C31") (pin "1") (pinfunction "1_1") (pintype "passive"))
      (node (ref "Q2") (pin "1") (pinfunction "1_1") (pintype "passive"))
      (node (ref "U1") (pin "7") (pinfunction "PB6/XTAL1/TOSC1_7") (pintype "bidirectional"))
    )
    (net (code "57") (name "Net-(U1-PB7{slash}XTAL2{slash}TOSC2)") (class "Default")
      (node (ref "C33") (pin "1") (pinfunction "1_1") (pintype "passive"))
      (node (ref "Q2") (pin "2") (pinfunction "2_2") (pintype "passive"))
      (node (ref "U1") (pin "8") (pinfunction "PB7/XTAL2/TOSC2_8") (pintype "bidirectional"))
    )
    (net (code "58") (name "RESET") (class "Default")
      (node (ref "U$8") (pin "5") (pinfunction "RESET_5") (pintype "input"))
    )
    (net (code "59") (name "RST") (class "Default")
      (node (ref "C1") (pin "1") (pinfunction "1_1") (pintype "passive"))
      (node (ref "ISP1") (pin "5") (pinfunction "RST_5") (pintype "output"))
      (node (ref "R3") (pin "1") (pinfunction "1_1") (pintype "passive"))
      (node (ref "S1") (pin "2") (pinfunction "2_2") (pintype "passive"))
      (node (ref "U1") (pin "29") (pinfunction "PC6/~{RESET}_29") (pintype "bidirectional"))
    )
    (net (code "60") (name "RX") (class "Default")
      (node (ref "JMP6") (pin "3") (pinfunction "3_3") (pintype "passive"))
      (node (ref "JMP7") (pin "1") (pinfunction "1_1") (pintype "passive"))
      (node (ref "U$11") (pin "4") (pinfunction "P$4_4") (pintype "bidirectional"))
      (node (ref "U1") (pin "30") (pinfunction "PD0/PTCXY/OC3A/RXD0_30") (pintype "bidirectional"))
    )
    (net (code "61") (name "RX1") (class "Default")
      (node (ref "ISP1") (pin "1") (pinfunction "MISO_1") (pintype "input"))
      (node (ref "U$12") (pin "3") (pinfunction "P$3_3") (pintype "bidirectional"))
      (node (ref "U1") (pin "16") (pinfunction "PB4/MISO0/RXD1/PTCXY_16") (pintype "bidirectional"))
    )
    (net (code "62") (name "SCL0") (class "Default")
      (node (ref "JMP1") (pin "3") (pinfunction "3_3") (pintype "passive"))
      (node (ref "U$7") (pin "3") (pinfunction "P$3_3") (pintype "bidirectional"))
      (node (ref "U1") (pin "28") (pinfunction "PC5/ADC5/PTCY/SCL0_28") (pintype "bidirectional"))
    )
    (net (code "63") (name "SCL1") (class "Default")
      (node (ref "JMP1") (pin "1") (pinfunction "1_1") (pintype "passive"))
      (node (ref "U1") (pin "6") (pinfunction "PE1/SCL1/T4/PTCXY_6") (pintype "bidirectional"))
    )
    (net (code "64") (name "SDA0") (class "Default")
      (node (ref "JMP2") (pin "3") (pinfunction "3_3") (pintype "passive"))
      (node (ref "U$7") (pin "4") (pinfunction "P$4_4") (pintype "bidirectional"))
      (node (ref "U1") (pin "27") (pinfunction "PC4/ADC4/PTCY/SDA0_27") (pintype "bidirectional"))
    )
    (net (code "65") (name "SDA1") (class "Default")
      (node (ref "JMP2") (pin "1") (pinfunction "1_1") (pintype "passive"))
      (node (ref "U1") (pin "3") (pinfunction "PE0/SDA1/ICP4/ACO/PTCXY_3") (pintype "bidirectional"))
    )
    (net (code "66") (name "TX") (class "Default")
      (node (ref "JMP6") (pin "1") (pinfunction "1_1") (pintype "passive"))
      (node (ref "JMP7") (pin "3") (pinfunction "3_3") (pintype "passive"))
      (node (ref "U$11") (pin "3") (pinfunction "P$3_3") (pintype "bidirectional"))
      (node (ref "U1") (pin "31") (pinfunction "PD1/PTCXY/OC4A/TXD0_31") (pintype "bidirectional"))
    )
    (net (code "67") (name "TX1") (class "Default")
      (node (ref "ISP1") (pin "4") (pinfunction "MOSI_4") (pintype "output"))
      (node (ref "U$12") (pin "4") (pinfunction "P$4_4") (pintype "bidirectional"))
      (node (ref "U1") (pin "15") (pinfunction "PB3/MOSI0/TXD1/OC2A/PTCXY_15") (pintype "bidirectional"))
    )
    (net (code "68") (name "UL2") (class "Default")
      (node (ref "U1") (pin "12") (pinfunction "PB0/ICP1/CLKO/PTCXY_12") (pintype "bidirectional"))
      (node (ref "U3") (pin "2") (pinfunction "ZB_2") (pintype "bidirectional"))
    )
    (net (code "69") (name "UL3") (class "Default")
      (node (ref "U1") (pin "13") (pinfunction "PB1/OC1A/PTCXY_13") (pintype "bidirectional"))
      (node (ref "U3") (pin "3") (pinfunction "SB_3") (pintype "bidirectional"))
    )
    (net (code "70") (name "VCC") (class "Default")
      (node (ref "C12") (pin "+") (pinfunction "+_+") (pintype "passive"))
      (node (ref "C3") (pin "1") (pinfunction "1_1") (pintype "passive"))
      (node (ref "C4") (pin "1") (pinfunction "1_1") (pintype "passive"))
      (node (ref "C6") (pin "1") (pinfunction "1_1") (pintype "passive"))
      (node (ref "C7") (pin "+") (pinfunction "+_+") (pintype "passive"))
      (node (ref "JMP10") (pin "3") (pinfunction "3_3") (pintype "passive"))
      (node (ref "JMP3") (pin "3") (pinfunction "3_3") (pintype "passive"))
      (node (ref "JMP5") (pin "3") (pinfunction "3_3") (pintype "passive"))
      (node (ref "JMP8") (pin "3") (pinfunction "3_3") (pintype "passive"))
      (node (ref "JMP9") (pin "3") (pinfunction "3_3") (pintype "passive"))
      (node (ref "R6") (pin "2") (pinfunction "2_2") (pintype "passive"))
      (node (ref "U$1") (pin "1") (pinfunction "P$1_1") (pintype "bidirectional"))
      (node (ref "U$10") (pin "1") (pinfunction "P$1_1") (pintype "bidirectional"))
      (node (ref "U4") (pin "3") (pinfunction "IN_3") (pintype "input"))
      (node (ref "U6") (pin "2") (pinfunction "OUT_2") (pintype "output"))
      (node (ref "U6") (pin "4") (pinfunction "4_4") (pintype "passive"))
    )
    (net (code "71") (name "VIN") (class "Default")
      (node (ref "C10") (pin "+") (pinfunction "+_+") (pintype "passive"))
      (node (ref "C14") (pin "+") (pinfunction "+_+") (pintype "passive"))
      (node (ref "C16") (pin "+") (pinfunction "+_+") (pintype "passive"))
      (node (ref "C18") (pin "+") (pinfunction "+_+") (pintype "passive"))
      (node (ref "C29") (pin "+") (pinfunction "+_+") (pintype "passive"))
      (node (ref "C9") (pin "1") (pinfunction "1_1") (pintype "passive"))
      (node (ref "D2") (pin "C") (pinfunction "C_C") (pintype "passive"))
      (node (ref "D4") (pin "C") (pinfunction "C_C") (pintype "passive"))
      (node (ref "D5") (pin "C") (pinfunction "C_C") (pintype "passive"))
      (node (ref "D6") (pin "C") (pinfunction "C_C") (pintype "passive"))
      (node (ref "D7") (pin "C") (pinfunction "C_C") (pintype "passive"))
      (node (ref "Q1") (pin "2") (pinfunction "S_2") (pintype "passive"))
      (node (ref "Q3") (pin "2") (pinfunction "S_2") (pintype "passive"))
      (node (ref "Q4") (pin "2") (pinfunction "S_2") (pintype "passive"))
      (node (ref "Q5") (pin "2") (pinfunction "S_2") (pintype "passive"))
      (node (ref "Q6") (pin "S") (pinfunction "S_S") (pintype "bidirectional"))
      (node (ref "R15") (pin "2") (pinfunction "2_2") (pintype "passive"))
      (node (ref "R17") (pin "2") (pinfunction "2_2") (pintype "passive"))
      (node (ref "R19") (pin "2") (pinfunction "2_2") (pintype "passive"))
      (node (ref "R40") (pin "2") (pinfunction "2_2") (pintype "passive"))
      (node (ref "R41") (pin "2") (pinfunction "2_2") (pintype "passive"))
      (node (ref "U$20") (pin "P$1") (pinfunction "1_P$1") (pintype "passive"))
      (node (ref "U$22") (pin "P$1") (pinfunction "1_P$1") (pintype "passive"))
      (node (ref "U3") (pin "9") (pinfunction "COM_9") (pintype "bidirectional"))
      (node (ref "U6") (pin "3") (pinfunction "IN_3") (pintype "input"))
    )
    (net (code "72") (name "unconnected-(J1-Pad5)") (class "Default")
      (node (ref "J1") (pin "5") (pinfunction "5_5") (pintype "passive"))
    )
    (net (code "73") (name "unconnected-(J1-Pad6)") (class "Default")
      (node (ref "J1") (pin "6") (pinfunction "6_6") (pintype "passive"))
    )
    (net (code "74") (name "unconnected-(J2-Pad5)") (class "Default")
      (node (ref "J2") (pin "5") (pinfunction "5_5") (pintype "passive"))
    )
    (net (code "75") (name "unconnected-(J2-Pad6)") (class "Default")
      (node (ref "J2") (pin "6") (pinfunction "6_6") (pintype "passive"))
    )
    (net (code "76") (name "unconnected-(J2-Pad7)") (class "Default")
      (node (ref "J2") (pin "7") (pinfunction "7_7") (pintype "passive"))
    )
    (net (code "77") (name "unconnected-(J2-Pad8)") (class "Default")
      (node (ref "J2") (pin "8") (pinfunction "8_8") (pintype "passive"))
    )
    (net (code "78") (name "unconnected-(U$8-AD0{slash}DIO0-Pad20)") (class "Default")
      (node (ref "U$8") (pin "20") (pinfunction "AD0/DIO0_20") (pintype "bidirectional"))
    )
    (net (code "79") (name "unconnected-(U$8-AD1{slash}DIO1-Pad19)") (class "Default")
      (node (ref "U$8") (pin "19") (pinfunction "AD1/DIO1_19") (pintype "bidirectional"))
    )
    (net (code "80") (name "unconnected-(U$8-AD2{slash}DIO2-Pad18)") (class "Default")
      (node (ref "U$8") (pin "18") (pinfunction "AD2/DIO2_18") (pintype "bidirectional"))
    )
    (net (code "81") (name "unconnected-(U$8-AD3{slash}DIO3-Pad17)") (class "Default")
      (node (ref "U$8") (pin "17") (pinfunction "AD3/DIO3_17") (pintype "bidirectional"))
    )
    (net (code "82") (name "unconnected-(U$8-AD4{slash}DIO4-Pad11)") (class "Default")
      (node (ref "U$8") (pin "11") (pinfunction "AD4/DIO4_11") (pintype "bidirectional"))
    )
    (net (code "83") (name "unconnected-(U$8-ASC{slash}AD5{slash}DIO5-Pad15)") (class "Default")
      (node (ref "U$8") (pin "15") (pinfunction "ASC/AD5/DIO5_15") (pintype "bidirectional"))
    )
    (net (code "84") (name "unconnected-(U$8-CTS{slash}DIO7-Pad12)") (class "Default")
      (node (ref "U$8") (pin "12") (pinfunction "CTS/DIO7_12") (pintype "bidirectional"))
    )
    (net (code "85") (name "unconnected-(U$8-DO8-Pad4)") (class "Default")
      (node (ref "U$8") (pin "4") (pinfunction "DO8_4") (pintype "output"))
    )
    (net (code "86") (name "unconnected-(U$8-DTR{slash}DI8-Pad9)") (class "Default")
      (node (ref "U$8") (pin "9") (pinfunction "DTR/DI8_9") (pintype "input"))
    )
    (net (code "87") (name "unconnected-(U$8-ON{slash}SLEEP-Pad13)") (class "Default")
      (node (ref "U$8") (pin "13") (pinfunction "ON/SLEEP_13") (pintype "output"))
    )
    (net (code "88") (name "unconnected-(U$8-PWM0{slash}RSSI-Pad6)") (class "Default")
      (node (ref "U$8") (pin "6") (pinfunction "PWM0/RSSI_6") (pintype "output"))
    )
    (net (code "89") (name "unconnected-(U$8-PWM1-Pad7)") (class "Default")
      (node (ref "U$8") (pin "7") (pinfunction "PWM1_7") (pintype "output"))
    )
    (net (code "90") (name "unconnected-(U$8-RESERVED-Pad8)") (class "Default")
      (node (ref "U$8") (pin "8") (pinfunction "RESERVED_8") (pintype "no_connect"))
    )
    (net (code "91") (name "unconnected-(U$8-RTS{slash}AD6{slash}DIO6-Pad16)") (class "Default")
      (node (ref "U$8") (pin "16") (pinfunction "RTS/AD6/DIO6_16") (pintype "bidirectional"))
    )
    (net (code "92") (name "unconnected-(U$8-VREF-Pad14)") (class "Default")
      (node (ref "U$8") (pin "14") (pinfunction "VREF_14") (pintype "input"))
    )
  )
)
